# Pressure-Sensor.net
KiCad netlist of a schematic drawn in Altium Designer
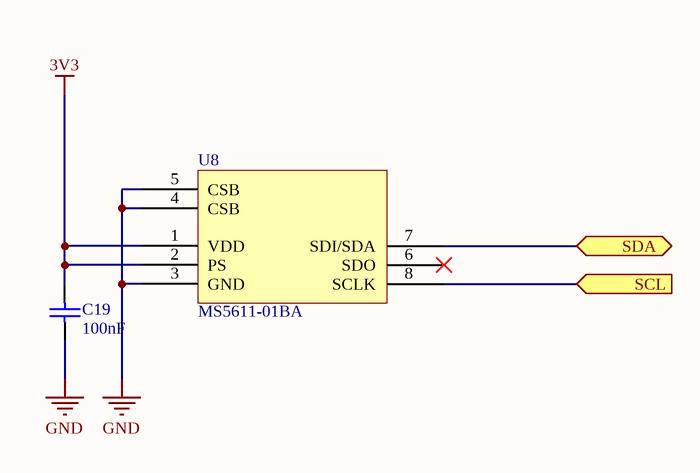
[diagram p0: Pressure-Sensor.SchDoc]

(export (version "E")
  (design (tool "Eeschema 10.0.6"))
  (components
    (comp (ref "C19")
      (value "100nF")
      (footprint "C0603(1608)")
      (description "Capacitor")
      (libsource (lib "Miscellaneous Devices") (part "Cap"))
    )
    (comp (ref "U8")
      (value "MS5611-01BA")
      (footprint "MS5611-01BA01")
      (description "Barometric Pressure Sensor")
      (libsource (lib "SCHlib") (part "SENSOR"))
    )
  )
  (nets
    (net (code "1") (name "/SCL") (class "Default")
      (node (ref "U8") (pin "8") (pinfunction "SCLK_8") (pintype "passive"))
    )
    (net (code "2") (name "/SDA") (class "Default")
      (node (ref "U8") (pin "7") (pinfunction "SDI/SDA_7") (pintype "passive"))
    )
    (net (code "3") (name "3V3") (class "Default")
      (node (ref "C19") (pin "2") (pinfunction "2_2") (pintype "passive"))
      (node (ref "U8") (pin "1") (pinfunction "VDD_1") (pintype "passive"))
      (node (ref "U8") (pin "2") (pinfunction "PS_2") (pintype "passive"))
    )
    (net (code "4") (name "GND") (class "Default")
      (node (ref "C19") (pin "1") (pinfunction "1_1") (pintype "passive"))
      (node (ref "U8") (pin "3") (pinfunction "GND_3") (pintype "passive"))
      (node (ref "U8") (pin "4") (pinfunction "CSB_4") (pintype "passive"))
      (node (ref "U8") (pin "5") (pinfunction "CSB_5") (pintype "passive"))
    )
    (net (code "5") (name "unconnected-(U8-SDO-Pad6)") (class "Default")
      (node (ref "U8") (pin "6") (pinfunction "SDO_6") (pintype "passive+no_connect"))
    )
  )
)
